# cpu.net
KiCad netlist of a schematic drawn in Altium Designer
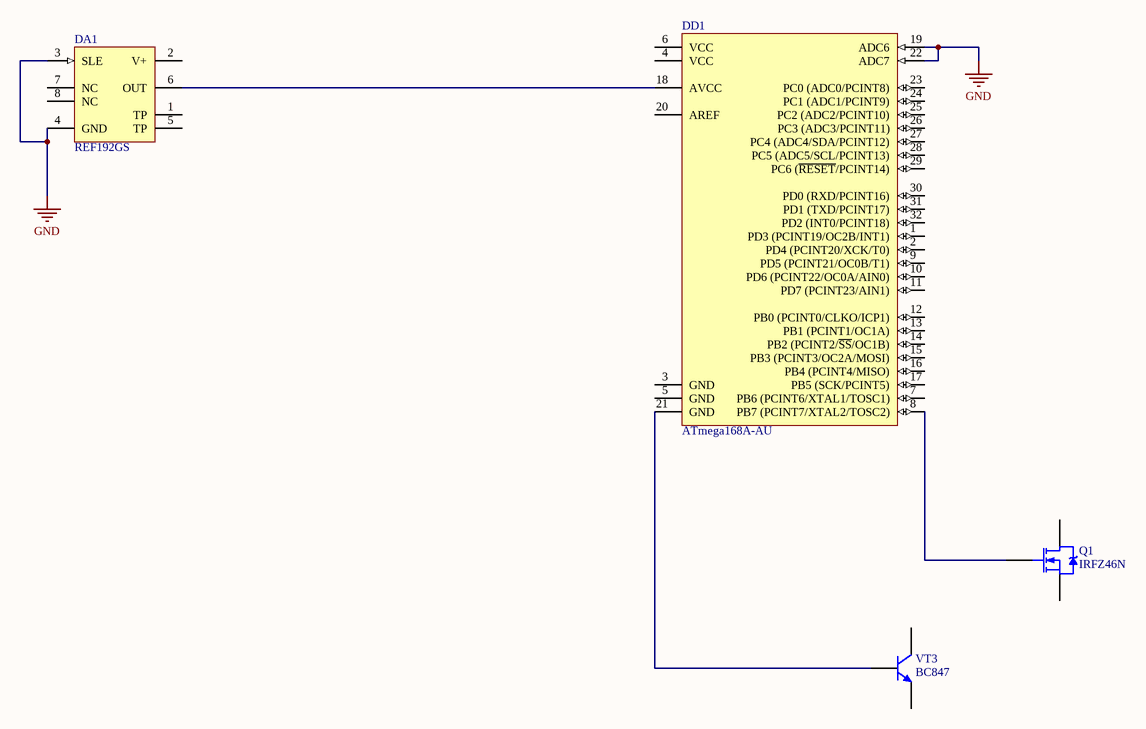
[diagram p0: cpu.SchDoc]

(export (version "E")
  (design (tool "Eeschema 10.0.6"))
  (components
    (comp (ref "DA1")
      (value "REF192GS")
      (footprint "SO-8_N")
      (description "2.50V, Precision Micropower, Low-Dropout, Voltage Reference")
      (fields (field (name "PUBLISHER") "Altium Limited"))
      (libsource (lib "AD Power Mgt Voltage Reference") (part "REF192GS"))
    )
    (comp (ref "DD1")
      (value "ATmega168A-AU")
      (footprint "32A_N")
      (fields (field (name "PUBLISHER") "Altium Limited"))
      (libsource (lib "Atmel Microcontroller 8-Bit megaAVR") (part "ATmega168A-AU"))
    )
    (comp (ref "Q1")
      (value "IRFZ46N")
      (footprint "TO-220AB")
      (description "HEXFET Power MOSFET")
      (fields (field (name "PUBLISHER") "Altium Limited"))
      (libsource (lib "IR Discrete MOSFET - Power") (part "IRFZ46N"))
    )
    (comp (ref "VT3")
      (value "BC847")
      (footprint "SOT23_N")
      (description "NPN General-purpose Transistor")
      (fields (field (name "PUBLISHER") "Altium Limited"))
      (libsource (lib "Philips Discrete BJT - Low Power") (part "BC847"))
    )
  )
  (nets
    (net (code "1") (name "GND") (class "Default")
      (node (ref "DA1") (pin "3") (pinfunction "SLE_3") (pintype "input"))
      (node (ref "DA1") (pin "4") (pinfunction "GND_4") (pintype "power_in"))
      (node (ref "DD1") (pin "19") (pinfunction "ADC6_19") (pintype "input"))
      (node (ref "DD1") (pin "22") (pinfunction "ADC7_22") (pintype "input"))
    )
    (net (code "2") (name "Net-(DA1-OUT)") (class "Default")
      (node (ref "DA1") (pin "6") (pinfunction "OUT_6") (pintype "power_in"))
      (node (ref "DD1") (pin "18") (pinfunction "AVCC_18") (pintype "power_in"))
    )
    (net (code "3") (name "Net-(DD1-PB7_(PCINT7{slash}XTAL2{slash}TOSC2))") (class "Default")
      (node (ref "DD1") (pin "8") (pinfunction "PB7_(PCINT7/XTAL2/TOSC2)_8") (pintype "bidirectional"))
      (node (ref "Q1") (pin "1") (pinfunction "G_1") (pintype "passive"))
    )
    (net (code "4") (name "Net-(VT3-B)") (class "Default")
      (node (ref "DD1") (pin "21") (pinfunction "GND_21") (pintype "power_in"))
      (node (ref "VT3") (pin "1") (pinfunction "B_1") (pintype "passive"))
    )
    (net (code "5") (name "unconnected-(DA1-NC-Pad7)") (class "Default")
      (node (ref "DA1") (pin "7") (pinfunction "NC_7") (pintype "passive"))
    )
    (net (code "6") (name "unconnected-(DA1-NC-Pad8)") (class "Default")
      (node (ref "DA1") (pin "8") (pinfunction "NC_8") (pintype "passive"))
    )
    (net (code "7") (name "unconnected-(DA1-TP-Pad1)") (class "Default")
      (node (ref "DA1") (pin "1") (pinfunction "TP_1") (pintype "passive"))
    )
    (net (code "8") (name "unconnected-(DA1-TP-Pad5)") (class "Default")
      (node (ref "DA1") (pin "5") (pinfunction "TP_5") (pintype "passive"))
    )
    (net (code "9") (name "unconnected-(DA1-V+-Pad2)") (class "Default")
      (node (ref "DA1") (pin "2") (pinfunction "V+_2") (pintype "power_in"))
    )
    (net (code "10") (name "unconnected-(DD1-AREF-Pad20)") (class "Default")
      (node (ref "DD1") (pin "20") (pinfunction "AREF_20") (pintype "passive"))
    )
    (net (code "11") (name "unconnected-(DD1-GND-Pad3)") (class "Default")
      (node (ref "DD1") (pin "3") (pinfunction "GND_3") (pintype "power_in"))
    )
    (net (code "12") (name "unconnected-(DD1-GND-Pad5)") (class "Default")
      (node (ref "DD1") (pin "5") (pinfunction "GND_5") (pintype "power_in"))
    )
    (net (code "13") (name "unconnected-(DD1-PB0_(PCINT0{slash}CLKO{slash}ICP1)-Pad12)") (class "Default")
      (node (ref "DD1") (pin "12") (pinfunction "PB0_(PCINT0/CLKO/ICP1)_12") (pintype "bidirectional"))
    )
    (net (code "14") (name "unconnected-(DD1-PB1_(PCINT1{slash}OC1A)-Pad13)") (class "Default")
      (node (ref "DD1") (pin "13") (pinfunction "PB1_(PCINT1/OC1A)_13") (pintype "bidirectional"))
    )
    (net (code "15") (name "unconnected-(DD1-PB2_(PCINT2{slash}~{SS}{slash}OC1B)-Pad14)") (class "Default")
      (node (ref "DD1") (pin "14") (pinfunction "PB2_(PCINT2/~{SS}/OC1B)_14") (pintype "bidirectional"))
    )
    (net (code "16") (name "unconnected-(DD1-PB3_(PCINT3{slash}OC2A{slash}MOSI)-Pad15)") (class "Default")
      (node (ref "DD1") (pin "15") (pinfunction "PB3_(PCINT3/OC2A/MOSI)_15") (pintype "bidirectional"))
    )
    (net (code "17") (name "unconnected-(DD1-PB4_(PCINT4{slash}MISO)-Pad16)") (class "Default")
      (node (ref "DD1") (pin "16") (pinfunction "PB4_(PCINT4/MISO)_16") (pintype "bidirectional"))
    )
    (net (code "18") (name "unconnected-(DD1-PB5_(SCK{slash}PCINT5)-Pad17)") (class "Default")
      (node (ref "DD1") (pin "17") (pinfunction "PB5_(SCK/PCINT5)_17") (pintype "bidirectional"))
    )
    (net (code "19") (name "unconnected-(DD1-PB6_(PCINT6{slash}XTAL1{slash}TOSC1)-Pad7)") (class "Default")
      (node (ref "DD1") (pin "7") (pinfunction "PB6_(PCINT6/XTAL1/TOSC1)_7") (pintype "bidirectional"))
    )
    (net (code "20") (name "unconnected-(DD1-PC0_(ADC0{slash}PCINT8)-Pad23)") (class "Default")
      (node (ref "DD1") (pin "23") (pinfunction "PC0_(ADC0/PCINT8)_23") (pintype "bidirectional"))
    )
    (net (code "21") (name "unconnected-(DD1-PC1_(ADC1{slash}PCINT9)-Pad24)") (class "Default")
      (node (ref "DD1") (pin "24") (pinfunction "PC1_(ADC1/PCINT9)_24") (pintype "bidirectional"))
    )
    (net (code "22") (name "unconnected-(DD1-PC2_(ADC2{slash}PCINT10)-Pad25)") (class "Default")
      (node (ref "DD1") (pin "25") (pinfunction "PC2_(ADC2/PCINT10)_25") (pintype "bidirectional"))
    )
    (net (code "23") (name "unconnected-(DD1-PC3_(ADC3{slash}PCINT11)-Pad26)") (class "Default")
      (node (ref "DD1") (pin "26") (pinfunction "PC3_(ADC3/PCINT11)_26") (pintype "bidirectional"))
    )
    (net (code "24") (name "unconnected-(DD1-PC4_(ADC4{slash}SDA{slash}PCINT12)-Pad27)") (class "Default")
      (node (ref "DD1") (pin "27") (pinfunction "PC4_(ADC4/SDA/PCINT12)_27") (pintype "bidirectional"))
    )
    (net (code "25") (name "unconnected-(DD1-PC5_(ADC5{slash}SCL{slash}PCINT13)-Pad28)") (class "Default")
      (node (ref "DD1") (pin "28") (pinfunction "PC5_(ADC5/SCL/PCINT13)_28") (pintype "bidirectional"))
    )
    (net (code "26") (name "unconnected-(DD1-PC6_(~{RESET}{slash}PCINT14)-Pad29)") (class "Default")
      (node (ref "DD1") (pin "29") (pinfunction "PC6_(~{RESET}/PCINT14)_29") (pintype "bidirectional"))
    )
    (net (code "27") (name "unconnected-(DD1-PD0_(RXD{slash}PCINT16)-Pad30)") (class "Default")
      (node (ref "DD1") (pin "30") (pinfunction "PD0_(RXD/PCINT16)_30") (pintype "bidirectional"))
    )
    (net (code "28") (name "unconnected-(DD1-PD1_(TXD{slash}PCINT17)-Pad31)") (class "Default")
      (node (ref "DD1") (pin "31") (pinfunction "PD1_(TXD/PCINT17)_31") (pintype "bidirectional"))
    )
    (net (code "29") (name "unconnected-(DD1-PD2_(INT0{slash}PCINT18)-Pad32)") (class "Default")
      (node (ref "DD1") (pin "32") (pinfunction "PD2_(INT0/PCINT18)_32") (pintype "bidirectional"))
    )
    (net (code "30") (name "unconnected-(DD1-PD3_(PCINT19{slash}OC2B{slash}INT1)-Pad1)") (class "Default")
      (node (ref "DD1") (pin "1") (pinfunction "PD3_(PCINT19/OC2B/INT1)_1") (pintype "bidirectional"))
    )
    (net (code "31") (name "unconnected-(DD1-PD4_(PCINT20{slash}XCK{slash}T0)-Pad2)") (class "Default")
      (node (ref "DD1") (pin "2") (pinfunction "PD4_(PCINT20/XCK/T0)_2") (pintype "bidirectional"))
    )
    (net (code "32") (name "unconnected-(DD1-PD5_(PCINT21{slash}OC0B{slash}T1)-Pad9)") (class "Default")
      (node (ref "DD1") (pin "9") (pinfunction "PD5_(PCINT21/OC0B/T1)_9") (pintype "bidirectional"))
    )
    (net (code "33") (name "unconnected-(DD1-PD6_(PCINT22{slash}OC0A{slash}AIN0)-Pad10)") (class "Default")
      (node (ref "DD1") (pin "10") (pinfunction "PD6_(PCINT22/OC0A/AIN0)_10") (pintype "bidirectional"))
    )
    (net (code "34") (name "unconnected-(DD1-PD7_(PCINT23{slash}AIN1)-Pad11)") (class "Default")
      (node (ref "DD1") (pin "11") (pinfunction "PD7_(PCINT23/AIN1)_11") (pintype "bidirectional"))
    )
    (net (code "35") (name "unconnected-(DD1-VCC-Pad4)") (class "Default")
      (node (ref "DD1") (pin "4") (pinfunction "VCC_4") (pintype "power_in"))
    )
    (net (code "36") (name "unconnected-(DD1-VCC-Pad6)") (class "Default")
      (node (ref "DD1") (pin "6") (pinfunction "VCC_6") (pintype "power_in"))
    )
    (net (code "37") (name "unconnected-(Q1-D-Pad2)") (class "Default")
      (node (ref "Q1") (pin "2") (pinfunction "D_2") (pintype "passive"))
    )
    (net (code "38") (name "unconnected-(Q1-S-Pad3)") (class "Default")
      (node (ref "Q1") (pin "3") (pinfunction "S_3") (pintype "passive"))
    )
    (net (code "39") (name "unconnected-(VT3-C-Pad3)") (class "Default")
      (node (ref "VT3") (pin "3") (pinfunction "C_3") (pintype "passive"))
    )
    (net (code "40") (name "unconnected-(VT3-E-Pad2)") (class "Default")
      (node (ref "VT3") (pin "2") (pinfunction "E_2") (pintype "passive"))
    )
  )
)
